# distortion-noise-and-ring-modulator-v1_2.net
KiCad netlist of a schematic drawn in EAGLE
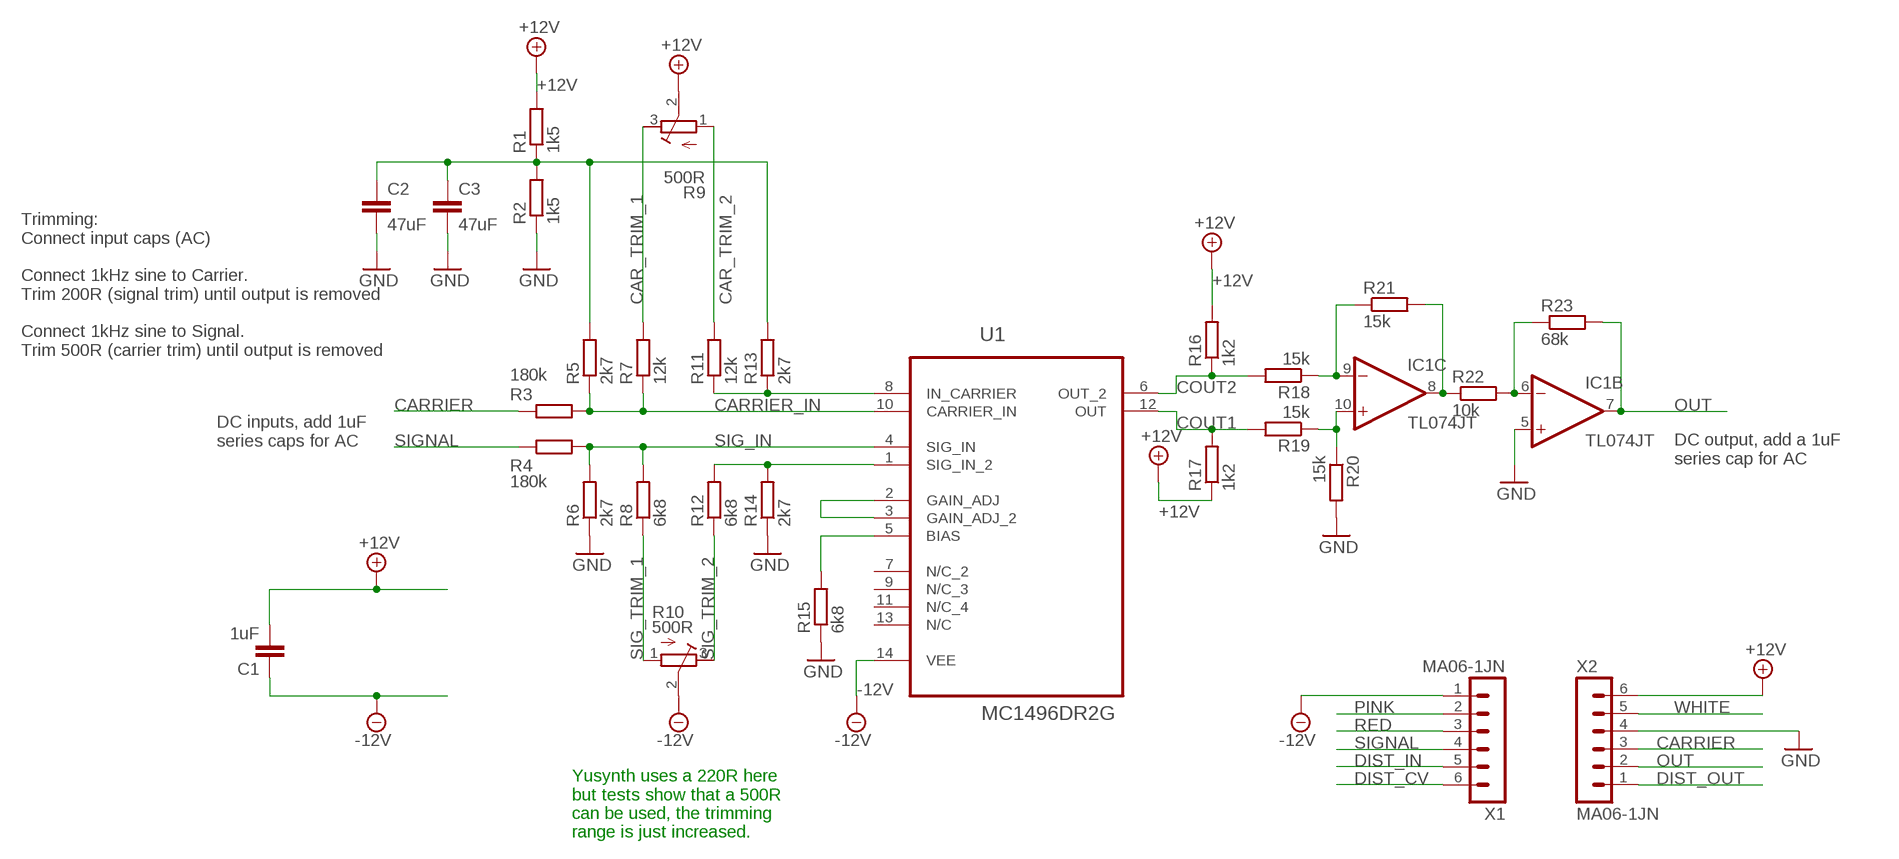
[diagram p0: schematic, sheet 1]
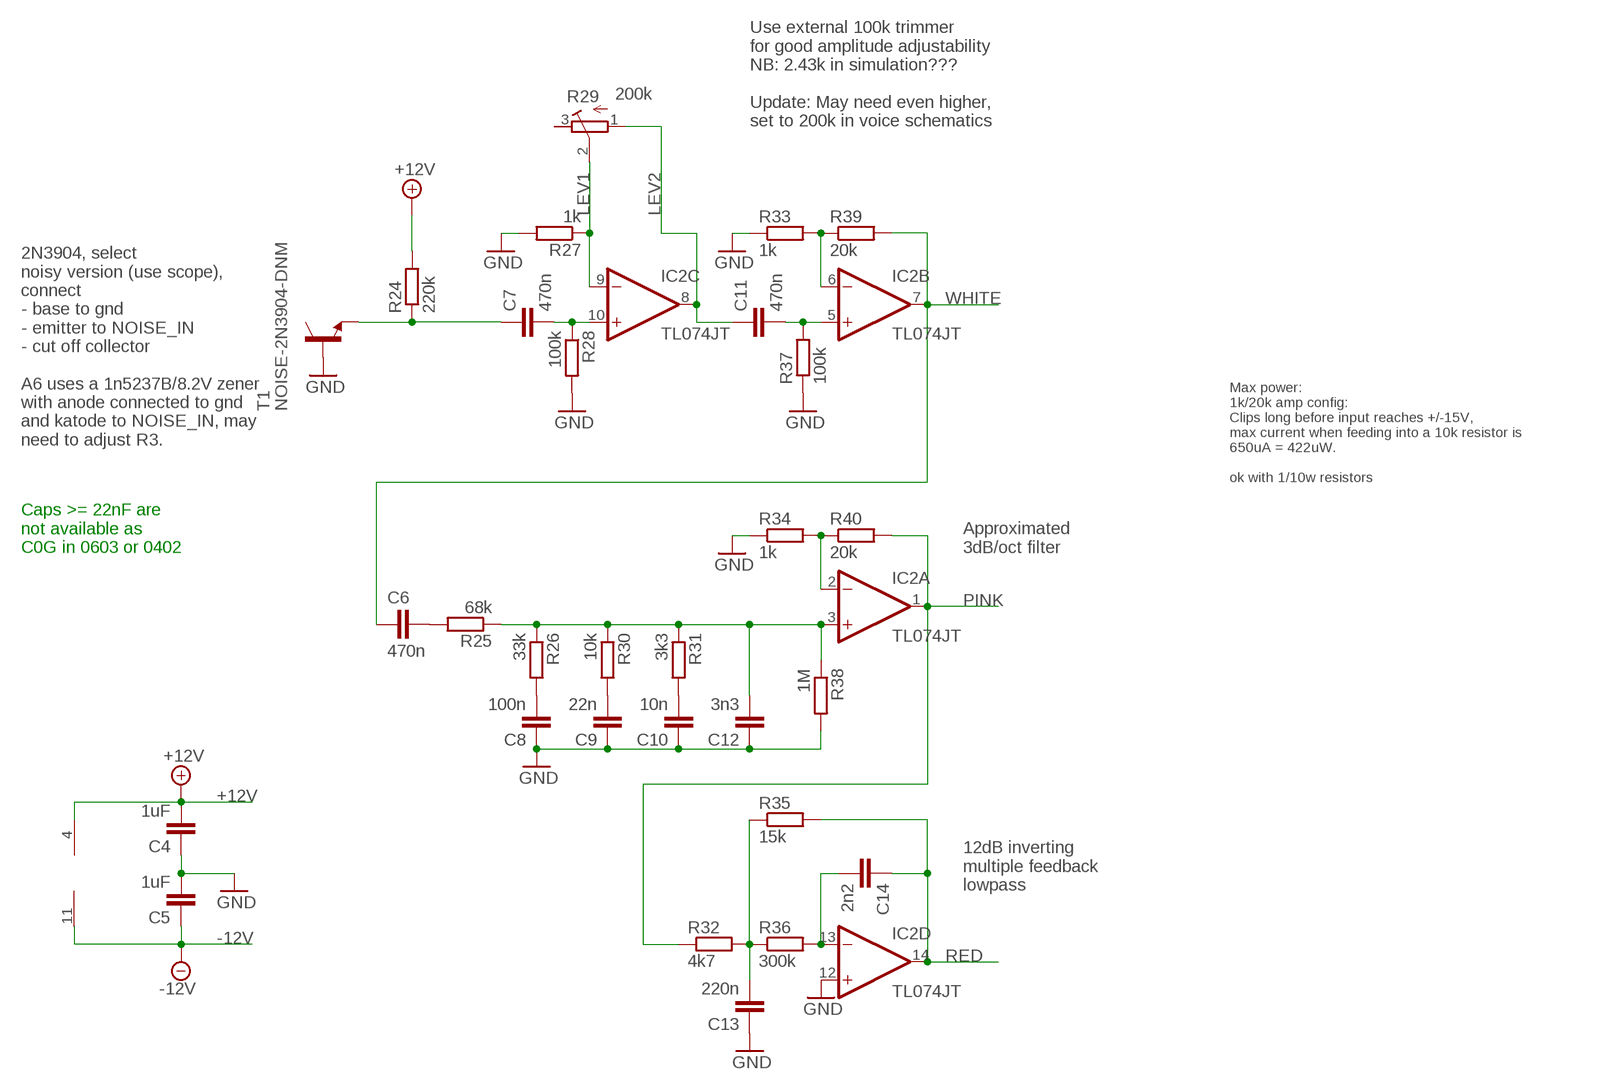
[diagram p1: schematic, sheet 2]
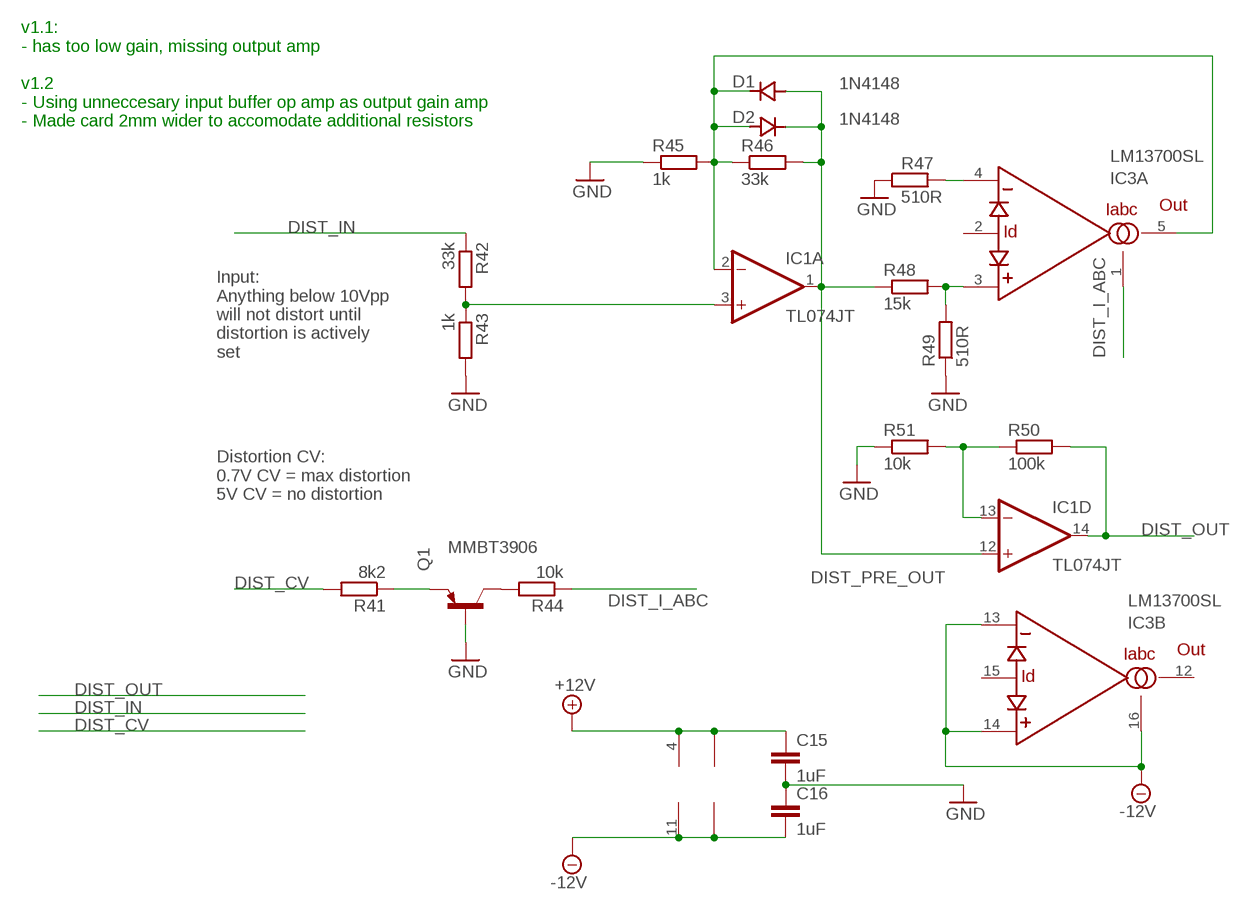
[diagram p2: schematic, sheet 3]

(export (version "E")
  (design (tool "Eeschema 10.0.6"))
  (components
    (comp (ref "C4")
      (value "1uF")
      (footprint "eagle-import:C0402-J")
      (libsource (lib "eagle-import") (part "C-EU-J0402"))
    )
    (comp (ref "C5")
      (value "1uF")
      (footprint "eagle-import:C0402-J")
      (libsource (lib "eagle-import") (part "C-EU-J0402"))
    )
    (comp (ref "C6")
      (value "470n")
      (footprint "eagle-import:C0603-J")
      (libsource (lib "eagle-import") (part "C-EU-J0603"))
    )
    (comp (ref "C7")
      (value "470n")
      (footprint "eagle-import:C0603-J")
      (libsource (lib "eagle-import") (part "C-EU-J0603"))
    )
    (comp (ref "C8")
      (value "100n")
      (footprint "eagle-import:C0402-J")
      (libsource (lib "eagle-import") (part "C-EU-J0402"))
    )
    (comp (ref "C9")
      (value "22n")
      (footprint "eagle-import:C0402-J")
      (libsource (lib "eagle-import") (part "C-EU-J0402"))
    )
    (comp (ref "C10")
      (value "10n")
      (footprint "eagle-import:C0402-J")
      (libsource (lib "eagle-import") (part "C-EU-J0402"))
    )
    (comp (ref "C11")
      (value "470n")
      (footprint "eagle-import:C0603-J")
      (libsource (lib "eagle-import") (part "C-EU-J0603"))
    )
    (comp (ref "C12")
      (value "3n3")
      (footprint "eagle-import:C0603-J")
      (libsource (lib "eagle-import") (part "C-EU-J0603"))
    )
    (comp (ref "C13")
      (value "220n")
      (footprint "eagle-import:C0402-J")
      (libsource (lib "eagle-import") (part "C-EU-J0402"))
    )
    (comp (ref "C14")
      (value "2n2")
      (footprint "eagle-import:C0603-J")
      (libsource (lib "eagle-import") (part "C-EU-J0603"))
    )
    (comp (ref "IC2")
      (value "TL074JT")
      (footprint "eagle-import:TSSOP14J")
      (libsource (lib "eagle-import") (part "TL074JT"))
    )
    (comp (ref "R24")
      (value "220k")
      (footprint "eagle-import:R0603")
      (libsource (lib "eagle-import") (part "R-EU_R0603"))
    )
    (comp (ref "R25")
      (value "68k")
      (footprint "eagle-import:R0603")
      (libsource (lib "eagle-import") (part "R-EU_R0603"))
    )
    (comp (ref "R26")
      (value "33k")
      (footprint "eagle-import:R0402")
      (libsource (lib "eagle-import") (part "R-EU_R0402"))
    )
    (comp (ref "R27")
      (value "1k")
      (footprint "eagle-import:R0402")
      (libsource (lib "eagle-import") (part "R-EU_R0402"))
    )
    (comp (ref "R28")
      (value "100k")
      (footprint "eagle-import:R0402")
      (libsource (lib "eagle-import") (part "R-EU_R0402"))
    )
    (comp (ref "R29")
      (value "200k")
      (footprint "eagle-import:RTRIM3296W")
      (libsource (lib "eagle-import") (part "R-TRIMM3296W"))
    )
    (comp (ref "R30")
      (value "10k")
      (footprint "eagle-import:R0402")
      (libsource (lib "eagle-import") (part "R-EU_R0402"))
    )
    (comp (ref "R31")
      (value "3k3")
      (footprint "eagle-import:R0402")
      (libsource (lib "eagle-import") (part "R-EU_R0402"))
    )
    (comp (ref "R32")
      (value "4k7")
      (footprint "eagle-import:R0402")
      (libsource (lib "eagle-import") (part "R-EU_R0402"))
    )
    (comp (ref "R33")
      (value "1k")
      (footprint "eagle-import:R0402")
      (libsource (lib "eagle-import") (part "R-EU_R0402"))
    )
    (comp (ref "R34")
      (value "1k")
      (footprint "eagle-import:R0402")
      (libsource (lib "eagle-import") (part "R-EU_R0402"))
    )
    (comp (ref "R35")
      (value "15k")
      (footprint "eagle-import:R0402")
      (libsource (lib "eagle-import") (part "R-EU_R0402"))
    )
    (comp (ref "R36")
      (value "300k")
      (footprint "eagle-import:R0603")
      (libsource (lib "eagle-import") (part "R-EU_R0603"))
    )
    (comp (ref "R37")
      (value "100k")
      (footprint "eagle-import:R0402")
      (libsource (lib "eagle-import") (part "R-EU_R0402"))
    )
    (comp (ref "R38")
      (value "1M")
      (footprint "eagle-import:R0402")
      (libsource (lib "eagle-import") (part "R-EU_R0402"))
    )
    (comp (ref "R39")
      (value "20k")
      (footprint "eagle-import:R0402")
      (libsource (lib "eagle-import") (part "R-EU_R0402"))
    )
    (comp (ref "R40")
      (value "20k")
      (footprint "eagle-import:R0402")
      (libsource (lib "eagle-import") (part "R-EU_R0402"))
    )
    (comp (ref "T1")
      (value "NOISE-2N3904-DNM")
      (footprint "eagle-import:NOISE-2N3904-J")
      (libsource (lib "eagle-import") (part "NOISE-2N3904"))
    )
    (comp (ref "C1")
      (value "1uF")
      (footprint "eagle-import:C0402-J")
      (libsource (lib "eagle-import") (part "C-EU-J0402"))
    )
    (comp (ref "C2")
      (value "47uF")
      (footprint "eagle-import:C1206")
      (libsource (lib "eagle-import") (part "C-EUC1206"))
    )
    (comp (ref "C3")
      (value "47uF")
      (footprint "eagle-import:C1206")
      (libsource (lib "eagle-import") (part "C-EUC1206"))
    )
    (comp (ref "IC1")
      (value "TL074JT")
      (footprint "eagle-import:TSSOP14J")
      (libsource (lib "eagle-import") (part "TL074JT"))
    )
    (comp (ref "R1")
      (value "1k5")
      (footprint "eagle-import:R0402")
      (libsource (lib "eagle-import") (part "R-EU_R0402"))
    )
    (comp (ref "R2")
      (value "1k5")
      (footprint "eagle-import:R0402")
      (libsource (lib "eagle-import") (part "R-EU_R0402"))
    )
    (comp (ref "R3")
      (value "180k")
      (footprint "eagle-import:R0402")
      (libsource (lib "eagle-import") (part "R-EU_R0402"))
    )
    (comp (ref "R4")
      (value "180k")
      (footprint "eagle-import:R0402")
      (libsource (lib "eagle-import") (part "R-EU_R0402"))
    )
    (comp (ref "R5")
      (value "2k7")
      (footprint "eagle-import:R0603")
      (libsource (lib "eagle-import") (part "R-EU_R0603"))
    )
    (comp (ref "R6")
      (value "2k7")
      (footprint "eagle-import:R0603")
      (libsource (lib "eagle-import") (part "R-EU_R0603"))
    )
    (comp (ref "R7")
      (value "12k")
      (footprint "eagle-import:R0402")
      (libsource (lib "eagle-import") (part "R-EU_R0402"))
    )
    (comp (ref "R8")
      (value "6k8")
      (footprint "eagle-import:R0603")
      (libsource (lib "eagle-import") (part "R-EU_R0603"))
    )
    (comp (ref "R9")
      (value "500R")
      (footprint "eagle-import:RTRIM3296X")
      (libsource (lib "eagle-import") (part "R-TRIMM3296X"))
    )
    (comp (ref "R10")
      (value "500R")
      (footprint "eagle-import:RTRIM3296X")
      (libsource (lib "eagle-import") (part "R-TRIMM3296X"))
    )
    (comp (ref "R11")
      (value "12k")
      (footprint "eagle-import:R0402")
      (libsource (lib "eagle-import") (part "R-EU_R0402"))
    )
    (comp (ref "R12")
      (value "6k8")
      (footprint "eagle-import:R0603")
      (libsource (lib "eagle-import") (part "R-EU_R0603"))
    )
    (comp (ref "R13")
      (value "2k7")
      (footprint "eagle-import:R0603")
      (libsource (lib "eagle-import") (part "R-EU_R0603"))
    )
    (comp (ref "R14")
      (value "2k7")
      (footprint "eagle-import:R0603")
      (libsource (lib "eagle-import") (part "R-EU_R0603"))
    )
    (comp (ref "R15")
      (value "6k8")
      (footprint "eagle-import:R0603")
      (libsource (lib "eagle-import") (part "R-EU_R0603"))
    )
    (comp (ref "R16")
      (value "1k2")
      (footprint "eagle-import:R0603")
      (libsource (lib "eagle-import") (part "R-EU_R0603"))
    )
    (comp (ref "R17")
      (value "1k2")
      (footprint "eagle-import:R0603")
      (libsource (lib "eagle-import") (part "R-EU_R0603"))
    )
    (comp (ref "R18")
      (value "15k")
      (footprint "eagle-import:R0402")
      (libsource (lib "eagle-import") (part "R-EU_R0402"))
    )
    (comp (ref "R19")
      (value "15k")
      (footprint "eagle-import:R0402")
      (libsource (lib "eagle-import") (part "R-EU_R0402"))
    )
    (comp (ref "R20")
      (value "15k")
      (footprint "eagle-import:R0402")
      (libsource (lib "eagle-import") (part "R-EU_R0402"))
    )
    (comp (ref "R21")
      (value "15k")
      (footprint "eagle-import:R0402")
      (libsource (lib "eagle-import") (part "R-EU_R0402"))
    )
    (comp (ref "R22")
      (value "10k")
      (footprint "eagle-import:R0402")
      (libsource (lib "eagle-import") (part "R-EU_R0402"))
    )
    (comp (ref "R23")
      (value "68k")
      (footprint "eagle-import:R0603")
      (libsource (lib "eagle-import") (part "R-EU_R0603"))
    )
    (comp (ref "U1")
      (value "MC1496DR2G")
      (footprint "eagle-import:SOIC127P600X175-14N")
      (libsource (lib "eagle-import") (part "MC1496DR2G"))
    )
    (comp (ref "X1")
      (value "MA06-1JN")
      (footprint "eagle-import:MA06N-1J")
      (libsource (lib "eagle-import") (part "MA06-1JN"))
    )
    (comp (ref "X2")
      (value "MA06-1JN")
      (footprint "eagle-import:MA06N-1J")
      (libsource (lib "eagle-import") (part "MA06-1JN"))
    )
    (comp (ref "C15")
      (value "1uF")
      (footprint "eagle-import:C0402-J")
      (libsource (lib "eagle-import") (part "C-EU-J0402"))
    )
    (comp (ref "C16")
      (value "1uF")
      (footprint "eagle-import:C0402-J")
      (libsource (lib "eagle-import") (part "C-EU-J0402"))
    )
    (comp (ref "D1")
      (value "1N4148")
      (footprint "eagle-import:SOD323J")
      (libsource (lib "eagle-import") (part "1N4148SOD323"))
    )
    (comp (ref "D2")
      (value "1N4148")
      (footprint "eagle-import:SOD323J")
      (libsource (lib "eagle-import") (part "1N4148SOD323"))
    )
    (comp (ref "IC3")
      (value "LM13700SL")
      (footprint "eagle-import:SO16-NARROW-J")
      (libsource (lib "eagle-import") (part "LM13700SL"))
    )
    (comp (ref "Q1")
      (value "MMBT3906")
      (footprint "eagle-import:SOT23-BEC")
      (libsource (lib "eagle-import") (part "MMBT3906SMDLT1"))
    )
    (comp (ref "R41")
      (value "8k2")
      (footprint "eagle-import:R0603")
      (libsource (lib "eagle-import") (part "R-EU_R0603"))
    )
    (comp (ref "R42")
      (value "33k")
      (footprint "eagle-import:R0402")
      (libsource (lib "eagle-import") (part "R-EU_R0402"))
    )
    (comp (ref "R43")
      (value "1k")
      (footprint "eagle-import:R0402")
      (libsource (lib "eagle-import") (part "R-EU_R0402"))
    )
    (comp (ref "R44")
      (value "10k")
      (footprint "eagle-import:R0402")
      (libsource (lib "eagle-import") (part "R-EU_R0402"))
    )
    (comp (ref "R45")
      (value "1k")
      (footprint "eagle-import:R0402")
      (libsource (lib "eagle-import") (part "R-EU_R0402"))
    )
    (comp (ref "R46")
      (value "33k")
      (footprint "eagle-import:R0402")
      (libsource (lib "eagle-import") (part "R-EU_R0402"))
    )
    (comp (ref "R47")
      (value "510R")
      (footprint "eagle-import:R0402")
      (libsource (lib "eagle-import") (part "R-EU_R0402"))
    )
    (comp (ref "R48")
      (value "15k")
      (footprint "eagle-import:R0402")
      (libsource (lib "eagle-import") (part "R-EU_R0402"))
    )
    (comp (ref "R49")
      (value "510R")
      (footprint "eagle-import:R0402")
      (libsource (lib "eagle-import") (part "R-EU_R0402"))
    )
    (comp (ref "R50")
      (value "100k")
      (footprint "eagle-import:R0402")
      (libsource (lib "eagle-import") (part "R-EU_R0402"))
    )
    (comp (ref "R51")
      (value "10k")
      (footprint "eagle-import:R0402")
      (libsource (lib "eagle-import") (part "R-EU_R0402"))
    )
  )
  (nets
    (net (code "1") (name "+12V") (class "Default")
      (node (ref "C1") (pin "2") (pinfunction "2_2") (pintype "passive"))
      (node (ref "C15") (pin "1") (pinfunction "1_1") (pintype "passive"))
      (node (ref "C4") (pin "2") (pinfunction "2_2") (pintype "passive"))
      (node (ref "IC1") (pin "4") (pinfunction "V+_4") (pintype "power_in"))
      (node (ref "IC2") (pin "4") (pinfunction "V+_4") (pintype "power_in"))
      (node (ref "IC3") (pin "11") (pinfunction "V+_11") (pintype "bidirectional"))
      (node (ref "R1") (pin "2") (pinfunction "2_2") (pintype "passive"))
      (node (ref "R16") (pin "2") (pinfunction "2_2") (pintype "passive"))
      (node (ref "R17") (pin "1") (pinfunction "1_1") (pintype "passive"))
      (node (ref "R24") (pin "2") (pinfunction "2_2") (pintype "passive"))
      (node (ref "R9") (pin "2") (pinfunction "S_2") (pintype "passive"))
      (node (ref "X2") (pin "6") (pinfunction "6_6") (pintype "passive"))
    )
    (net (code "2") (name "-12V") (class "Default")
      (node (ref "C1") (pin "1") (pinfunction "1_1") (pintype "passive"))
      (node (ref "C16") (pin "2") (pinfunction "2_2") (pintype "passive"))
      (node (ref "C5") (pin "1") (pinfunction "1_1") (pintype "passive"))
      (node (ref "IC1") (pin "11") (pinfunction "V-_11") (pintype "power_in"))
      (node (ref "IC2") (pin "11") (pinfunction "V-_11") (pintype "power_in"))
      (node (ref "IC3") (pin "13") (pinfunction "-IN_13") (pintype "bidirectional"))
      (node (ref "IC3") (pin "14") (pinfunction "+IN_14") (pintype "bidirectional"))
      (node (ref "IC3") (pin "16") (pinfunction "IABC_16") (pintype "bidirectional"))
      (node (ref "IC3") (pin "6") (pinfunction "V-_6") (pintype "bidirectional"))
      (node (ref "R10") (pin "2") (pinfunction "S_2") (pintype "passive"))
      (node (ref "U1") (pin "14") (pinfunction "VEE_14") (pintype "passive"))
      (node (ref "X1") (pin "1") (pinfunction "1_1") (pintype "passive"))
    )
    (net (code "3") (name "CARRIER") (class "Default")
      (node (ref "R3") (pin "1") (pinfunction "1_1") (pintype "passive"))
      (node (ref "X2") (pin "3") (pinfunction "3_3") (pintype "passive"))
    )
    (net (code "4") (name "CARRIER_IN") (class "Default")
      (node (ref "R3") (pin "2") (pinfunction "2_2") (pintype "passive"))
      (node (ref "R5") (pin "1") (pinfunction "1_1") (pintype "passive"))
      (node (ref "R7") (pin "1") (pinfunction "1_1") (pintype "passive"))
      (node (ref "U1") (pin "10") (pinfunction "CARRIER_IN_10") (pintype "power_in"))
    )
    (net (code "5") (name "CAR_TRIM_1") (class "Default")
      (node (ref "R7") (pin "2") (pinfunction "2_2") (pintype "passive"))
      (node (ref "R9") (pin "3") (pinfunction "E_3") (pintype "passive"))
    )
    (net (code "6") (name "CAR_TRIM_2") (class "Default")
      (node (ref "R11") (pin "2") (pinfunction "2_2") (pintype "passive"))
      (node (ref "R9") (pin "1") (pinfunction "A_1") (pintype "passive"))
    )
    (net (code "7") (name "COUT1") (class "Default")
      (node (ref "R17") (pin "2") (pinfunction "2_2") (pintype "passive"))
      (node (ref "R19") (pin "2") (pinfunction "2_2") (pintype "passive"))
      (node (ref "U1") (pin "12") (pinfunction "OUT_12") (pintype "output"))
    )
    (net (code "8") (name "COUT2") (class "Default")
      (node (ref "R16") (pin "1") (pinfunction "1_1") (pintype "passive"))
      (node (ref "R18") (pin "2") (pinfunction "2_2") (pintype "passive"))
      (node (ref "U1") (pin "6") (pinfunction "OUT_2_6") (pintype "output"))
    )
    (net (code "9") (name "DIST_CV") (class "Default")
      (node (ref "R41") (pin "2") (pinfunction "2_2") (pintype "passive"))
      (node (ref "X1") (pin "6") (pinfunction "6_6") (pintype "passive"))
    )
    (net (code "10") (name "DIST_IN") (class "Default")
      (node (ref "R42") (pin "1") (pinfunction "1_1") (pintype "passive"))
      (node (ref "X1") (pin "5") (pinfunction "5_5") (pintype "passive"))
    )
    (net (code "11") (name "DIST_I_ABC") (class "Default")
      (node (ref "IC3") (pin "1") (pinfunction "IABC_1") (pintype "bidirectional"))
      (node (ref "R44") (pin "1") (pinfunction "1_1") (pintype "passive"))
    )
    (net (code "12") (name "DIST_OUT") (class "Default")
      (node (ref "IC1") (pin "14") (pinfunction "OUT_14") (pintype "output"))
      (node (ref "R50") (pin "2") (pinfunction "2_2") (pintype "passive"))
      (node (ref "X2") (pin "1") (pinfunction "1_1") (pintype "passive"))
    )
    (net (code "13") (name "DIST_PRE_OUT") (class "Default")
      (node (ref "D1") (pin "2") (pinfunction "A_2") (pintype "passive"))
      (node (ref "D2") (pin "1") (pinfunction "C_1") (pintype "passive"))
      (node (ref "IC1") (pin "1") (pinfunction "OUT_1") (pintype "output"))
      (node (ref "IC1") (pin "12") (pinfunction "+IN_12") (pintype "input"))
      (node (ref "R46") (pin "2") (pinfunction "2_2") (pintype "passive"))
      (node (ref "R48") (pin "1") (pinfunction "1_1") (pintype "passive"))
    )
    (net (code "14") (name "GND") (class "Default")
      (node (ref "C10") (pin "1") (pinfunction "1_1") (pintype "passive"))
      (node (ref "C12") (pin "1") (pinfunction "1_1") (pintype "passive"))
      (node (ref "C13") (pin "1") (pinfunction "1_1") (pintype "passive"))
      (node (ref "C15") (pin "2") (pinfunction "2_2") (pintype "passive"))
      (node (ref "C16") (pin "1") (pinfunction "1_1") (pintype "passive"))
      (node (ref "C2") (pin "2") (pinfunction "2_2") (pintype "passive"))
      (node (ref "C3") (pin "2") (pinfunction "2_2") (pintype "passive"))
      (node (ref "C4") (pin "1") (pinfunction "1_1") (pintype "passive"))
      (node (ref "C5") (pin "2") (pinfunction "2_2") (pintype "passive"))
      (node (ref "C8") (pin "1") (pinfunction "1_1") (pintype "passive"))
      (node (ref "C9") (pin "1") (pinfunction "1_1") (pintype "passive"))
      (node (ref "IC1") (pin "5") (pinfunction "+IN_5") (pintype "input"))
      (node (ref "IC2") (pin "12") (pinfunction "+IN_12") (pintype "input"))
      (node (ref "Q1") (pin "B") (pinfunction "B_B") (pintype "passive"))
      (node (ref "R14") (pin "1") (pinfunction "1_1") (pintype "passive"))
      (node (ref "R15") (pin "1") (pinfunction "1_1") (pintype "passive"))
      (node (ref "R2") (pin "1") (pinfunction "1_1") (pintype "passive"))
      (node (ref "R20") (pin "2") (pinfunction "2_2") (pintype "passive"))
      (node (ref "R27") (pin "2") (pinfunction "2_2") (pintype "passive"))
      (node (ref "R28") (pin "2") (pinfunction "2_2") (pintype "passive"))
      (node (ref "R33") (pin "1") (pinfunction "1_1") (pintype "passive"))
      (node (ref "R34") (pin "1") (pinfunction "1_1") (pintype "passive"))
      (node (ref "R37") (pin "1") (pinfunction "1_1") (pintype "passive"))
      (node (ref "R38") (pin "2") (pinfunction "2_2") (pintype "passive"))
      (node (ref "R43") (pin "2") (pinfunction "2_2") (pintype "passive"))
      (node (ref "R45") (pin "1") (pinfunction "1_1") (pintype "passive"))
      (node (ref "R47") (pin "1") (pinfunction "1_1") (pintype "passive"))
      (node (ref "R49") (pin "1") (pinfunction "1_1") (pintype "passive"))
      (node (ref "R51") (pin "1") (pinfunction "1_1") (pintype "passive"))
      (node (ref "R6") (pin "1") (pinfunction "1_1") (pintype "passive"))
      (node (ref "T1") (pin "B") (pinfunction "B_B") (pintype "passive"))
      (node (ref "X2") (pin "4") (pinfunction "4_4") (pintype "passive"))
    )
    (net (code "15") (name "LEV1") (class "Default")
      (node (ref "IC2") (pin "9") (pinfunction "-IN_9") (pintype "input"))
      (node (ref "R27") (pin "1") (pinfunction "1_1") (pintype "passive"))
      (node (ref "R29") (pin "2") (pinfunction "S_2") (pintype "passive"))
    )
    (net (code "16") (name "LEV2") (class "Default")
      (node (ref "C11") (pin "1") (pinfunction "1_1") (pintype "passive"))
      (node (ref "IC2") (pin "8") (pinfunction "OUT_8") (pintype "output"))
      (node (ref "R29") (pin "1") (pinfunction "A_1") (pintype "passive"))
    )
    (net (code "17") (name "Net-(C2-Pad1)") (class "Default")
      (node (ref "C2") (pin "1") (pinfunction "1_1") (pintype "passive"))
      (node (ref "C3") (pin "1") (pinfunction "1_1") (pintype "passive"))
      (node (ref "R1") (pin "1") (pinfunction "1_1") (pintype "passive"))
      (node (ref "R13") (pin "2") (pinfunction "2_2") (pintype "passive"))
      (node (ref "R2") (pin "2") (pinfunction "2_2") (pintype "passive"))
      (node (ref "R5") (pin "2") (pinfunction "2_2") (pintype "passive"))
    )
    (net (code "18") (name "Net-(C6-Pad2)") (class "Default")
      (node (ref "C6") (pin "2") (pinfunction "2_2") (pintype "passive"))
      (node (ref "R25") (pin "2") (pinfunction "2_2") (pintype "passive"))
    )
    (net (code "19") (name "Net-(C7-Pad1)") (class "Default")
      (node (ref "C7") (pin "1") (pinfunction "1_1") (pintype "passive"))
      (node (ref "R24") (pin "1") (pinfunction "1_1") (pintype "passive"))
      (node (ref "T1") (pin "E") (pinfunction "E_E") (pintype "passive"))
    )
    (net (code "20") (name "Net-(C8-Pad2)") (class "Default")
      (node (ref "C8") (pin "2") (pinfunction "2_2") (pintype "passive"))
      (node (ref "R26") (pin "2") (pinfunction "2_2") (pintype "passive"))
    )
    (net (code "21") (name "Net-(C9-Pad2)") (class "Default")
      (node (ref "C9") (pin "2") (pinfunction "2_2") (pintype "passive"))
      (node (ref "R30") (pin "2") (pinfunction "2_2") (pintype "passive"))
    )
    (net (code "22") (name "Net-(C10-Pad2)") (class "Default")
      (node (ref "C10") (pin "2") (pinfunction "2_2") (pintype "passive"))
      (node (ref "R31") (pin "2") (pinfunction "2_2") (pintype "passive"))
    )
    (net (code "23") (name "Net-(C13-Pad2)") (class "Default")
      (node (ref "C13") (pin "2") (pinfunction "2_2") (pintype "passive"))
      (node (ref "R32") (pin "2") (pinfunction "2_2") (pintype "passive"))
      (node (ref "R35") (pin "1") (pinfunction "1_1") (pintype "passive"))
      (node (ref "R36") (pin "1") (pinfunction "1_1") (pintype "passive"))
    )
    (net (code "24") (name "Net-(D1-C)") (class "Default")
      (node (ref "D1") (pin "1") (pinfunction "C_1") (pintype "passive"))
      (node (ref "D2") (pin "2") (pinfunction "A_2") (pintype "passive"))
      (node (ref "IC1") (pin "2") (pinfunction "-IN_2") (pintype "input"))
      (node (ref "IC3") (pin "5") (pinfunction "OUT_5") (pintype "bidirectional"))
      (node (ref "R45") (pin "2") (pinfunction "2_2") (pintype "passive"))
      (node (ref "R46") (pin "1") (pinfunction "1_1") (pintype "passive"))
    )
    (net (code "25") (name "Net-(IC1A-+IN)") (class "Default")
      (node (ref "IC1") (pin "3") (pinfunction "+IN_3") (pintype "input"))
      (node (ref "R42") (pin "2") (pinfunction "2_2") (pintype "passive"))
      (node (ref "R43") (pin "1") (pinfunction "1_1") (pintype "passive"))
    )
    (net (code "26") (name "Net-(IC1B--IN)") (class "Default")
      (node (ref "IC1") (pin "6") (pinfunction "-IN_6") (pintype "input"))
      (node (ref "R22") (pin "2") (pinfunction "2_2") (pintype "passive"))
      (node (ref "R23") (pin "1") (pinfunction "1_1") (pintype "passive"))
    )
    (net (code "27") (name "Net-(IC1C-+IN)") (class "Default")
      (node (ref "IC1") (pin "10") (pinfunction "+IN_10") (pintype "input"))
      (node (ref "R19") (pin "1") (pinfunction "1_1") (pintype "passive"))
      (node (ref "R20") (pin "1") (pinfunction "1_1") (pintype "passive"))
    )
    (net (code "28") (name "Net-(IC1C--IN)") (class "Default")
      (node (ref "IC1") (pin "9") (pinfunction "-IN_9") (pintype "input"))
      (node (ref "R18") (pin "1") (pinfunction "1_1") (pintype "passive"))
      (node (ref "R21") (pin "1") (pinfunction "1_1") (pintype "passive"))
    )
    (net (code "29") (name "Net-(IC1C-OUT)") (class "Default")
      (node (ref "IC1") (pin "8") (pinfunction "OUT_8") (pintype "output"))
      (node (ref "R21") (pin "2") (pinfunction "2_2") (pintype "passive"))
      (node (ref "R22") (pin "1") (pinfunction "1_1") (pintype "passive"))
    )
    (net (code "30") (name "Net-(IC1D--IN)") (class "Default")
      (node (ref "IC1") (pin "13") (pinfunction "-IN_13") (pintype "input"))
      (node (ref "R50") (pin "1") (pinfunction "1_1") (pintype "passive"))
      (node (ref "R51") (pin "2") (pinfunction "2_2") (pintype "passive"))
    )
    (net (code "31") (name "Net-(IC2A-+IN)") (class "Default")
      (node (ref "C12") (pin "2") (pinfunction "2_2") (pintype "passive"))
      (node (ref "IC2") (pin "3") (pinfunction "+IN_3") (pintype "input"))
      (node (ref "R25") (pin "1") (pinfunction "1_1") (pintype "passive"))
      (node (ref "R26") (pin "1") (pinfunction "1_1") (pintype "passive"))
      (node (ref "R30") (pin "1") (pinfunction "1_1") (pintype "passive"))
      (node (ref "R31") (pin "1") (pinfunction "1_1") (pintype "passive"))
      (node (ref "R38") (pin "1") (pinfunction "1_1") (pintype "passive"))
    )
    (net (code "32") (name "Net-(IC2A--IN)") (class "Default")
      (node (ref "IC2") (pin "2") (pinfunction "-IN_2") (pintype "input"))
      (node (ref "R34") (pin "2") (pinfunction "2_2") (pintype "passive"))
      (node (ref "R40") (pin "1") (pinfunction "1_1") (pintype "passive"))
    )
    (net (code "33") (name "Net-(IC2B-+IN)") (class "Default")
      (node (ref "C11") (pin "2") (pinfunction "2_2") (pintype "passive"))
      (node (ref "IC2") (pin "5") (pinfunction "+IN_5") (pintype "input"))
      (node (ref "R37") (pin "2") (pinfunction "2_2") (pintype "passive"))
    )
    (net (code "34") (name "Net-(IC2B--IN)") (class "Default")
      (node (ref "IC2") (pin "6") (pinfunction "-IN_6") (pintype "input"))
      (node (ref "R33") (pin "2") (pinfunction "2_2") (pintype "passive"))
      (node (ref "R39") (pin "1") (pinfunction "1_1") (pintype "passive"))
    )
    (net (code "35") (name "Net-(IC2C-+IN)") (class "Default")
      (node (ref "C7") (pin "2") (pinfunction "2_2") (pintype "passive"))
      (node (ref "IC2") (pin "10") (pinfunction "+IN_10") (pintype "input"))
      (node (ref "R28") (pin "1") (pinfunction "1_1") (pintype "passive"))
    )
    (net (code "36") (name "Net-(IC2D--IN)") (class "Default")
      (node (ref "C14") (pin "2") (pinfunction "2_2") (pintype "passive"))
      (node (ref "IC2") (pin "13") (pinfunction "-IN_13") (pintype "input"))
      (node (ref "R36") (pin "2") (pinfunction "2_2") (pintype "passive"))
    )
    (net (code "37") (name "Net-(IC3A-+IN)") (class "Default")
      (node (ref "IC3") (pin "3") (pinfunction "+IN_3") (pintype "bidirectional"))
      (node (ref "R48") (pin "2") (pinfunction "2_2") (pintype "passive"))
      (node (ref "R49") (pin "2") (pinfunction "2_2") (pintype "passive"))
    )
    (net (code "38") (name "Net-(IC3A--IN)") (class "Default")
      (node (ref "IC3") (pin "4") (pinfunction "-IN_4") (pintype "bidirectional"))
      (node (ref "R47") (pin "2") (pinfunction "2_2") (pintype "passive"))
    )
    (net (code "39") (name "Net-(Q1-PadC)") (class "Default")
      (node (ref "Q1") (pin "C") (pinfunction "C_C") (pintype "passive"))
      (node (ref "R44") (pin "2") (pinfunction "2_2") (pintype "passive"))
    )
    (net (code "40") (name "Net-(Q1-PadE)") (class "Default")
      (node (ref "Q1") (pin "E") (pinfunction "E_E") (pintype "passive"))
      (node (ref "R41") (pin "1") (pinfunction "1_1") (pintype "passive"))
    )
    (net (code "41") (name "Net-(U1-BIAS)") (class "Default")
      (node (ref "R15") (pin "2") (pinfunction "2_2") (pintype "passive"))
      (node (ref "U1") (pin "5") (pinfunction "BIAS_5") (pintype "input"))
    )
    (net (code "42") (name "Net-(U1-GAIN_ADJ)") (class "Default")
      (node (ref "U1") (pin "2") (pinfunction "GAIN_ADJ_2") (pintype "input"))
      (node (ref "U1") (pin "3") (pinfunction "GAIN_ADJ_2_3") (pintype "input"))
    )
    (net (code "43") (name "Net-(U1-IN_CARRIER)") (class "Default")
      (node (ref "R11") (pin "1") (pinfunction "1_1") (pintype "passive"))
      (node (ref "R13") (pin "1") (pinfunction "1_1") (pintype "passive"))
      (node (ref "U1") (pin "8") (pinfunction "IN_CARRIER_8") (pintype "power_in"))
    )
    (net (code "44") (name "Net-(U1-SIG_IN_2)") (class "Default")
      (node (ref "R12") (pin "2") (pinfunction "2_2") (pintype "passive"))
      (node (ref "R14") (pin "2") (pinfunction "2_2") (pintype "passive"))
      (node (ref "U1") (pin "1") (pinfunction "SIG_IN_2_1") (pintype "input"))
    )
    (net (code "45") (name "OUT") (class "Default")
      (node (ref "IC1") (pin "7") (pinfunction "OUT_7") (pintype "output"))
      (node (ref "R23") (pin "2") (pinfunction "2_2") (pintype "passive"))
      (node (ref "X2") (pin "2") (pinfunction "2_2") (pintype "passive"))
    )
    (net (code "46") (name "PINK") (class "Default")
      (node (ref "IC2") (pin "1") (pinfunction "OUT_1") (pintype "output"))
      (node (ref "R32") (pin "1") (pinfunction "1_1") (pintype "passive"))
      (node (ref "R40") (pin "2") (pinfunction "2_2") (pintype "passive"))
      (node (ref "X1") (pin "2") (pinfunction "2_2") (pintype "passive"))
    )
    (net (code "47") (name "RED") (class "Default")
      (node (ref "C14") (pin "1") (pinfunction "1_1") (pintype "passive"))
      (node (ref "IC2") (pin "14") (pinfunction "OUT_14") (pintype "output"))
      (node (ref "R35") (pin "2") (pinfunction "2_2") (pintype "passive"))
      (node (ref "X1") (pin "3") (pinfunction "3_3") (pintype "passive"))
    )
    (net (code "48") (name "SIGNAL") (class "Default")
      (node (ref "R4") (pin "1") (pinfunction "1_1") (pintype "passive"))
      (node (ref "X1") (pin "4") (pinfunction "4_4") (pintype "passive"))
    )
    (net (code "49") (name "SIG_IN") (class "Default")
      (node (ref "R4") (pin "2") (pinfunction "2_2") (pintype "passive"))
      (node (ref "R6") (pin "2") (pinfunction "2_2") (pintype "passive"))
      (node (ref "R8") (pin "2") (pinfunction "2_2") (pintype "passive"))
      (node (ref "U1") (pin "4") (pinfunction "SIG_IN_4") (pintype "input"))
    )
    (net (code "50") (name "SIG_TRIM_1") (class "Default")
      (node (ref "R10") (pin "1") (pinfunction "A_1") (pintype "passive"))
      (node (ref "R8") (pin "1") (pinfunction "1_1") (pintype "passive"))
    )
    (net (code "51") (name "SIG_TRIM_2") (class "Default")
      (node (ref "R10") (pin "3") (pinfunction "E_3") (pintype "passive"))
      (node (ref "R12") (pin "1") (pinfunction "1_1") (pintype "passive"))
    )
    (net (code "52") (name "WHITE") (class "Default")
      (node (ref "C6") (pin "1") (pinfunction "1_1") (pintype "passive"))
      (node (ref "IC2") (pin "7") (pinfunction "OUT_7") (pintype "output"))
      (node (ref "R39") (pin "2") (pinfunction "2_2") (pintype "passive"))
      (node (ref "X2") (pin "5") (pinfunction "5_5") (pintype "passive"))
    )
    (net (code "53") (name "unconnected-(IC3A-ID-Pad2)") (class "Default")
      (node (ref "IC3") (pin "2") (pinfunction "ID_2") (pintype "bidirectional"))
    )
    (net (code "54") (name "unconnected-(IC3B-ID-Pad15)") (class "Default")
      (node (ref "IC3") (pin "15") (pinfunction "ID_15") (pintype "bidirectional"))
    )
    (net (code "55") (name "unconnected-(IC3B-OUT-Pad12)") (class "Default")
      (node (ref "IC3") (pin "12") (pinfunction "OUT_12") (pintype "bidirectional"))
    )
    (net (code "56") (name "unconnected-(R29-E-Pad3)") (class "Default")
      (node (ref "R29") (pin "3") (pinfunction "E_3") (pintype "passive"))
    )
    (net (code "57") (name "unconnected-(U1-N{slash}C-Pad13)") (class "Default")
      (node (ref "U1") (pin "13") (pinfunction "N/C_13") (pintype "no_connect"))
    )
    (net (code "58") (name "unconnected-(U1-N{slash}C_2-Pad7)") (class "Default")
      (node (ref "U1") (pin "7") (pinfunction "N/C_2_7") (pintype "no_connect"))
    )
    (net (code "59") (name "unconnected-(U1-N{slash}C_3-Pad9)") (class "Default")
      (node (ref "U1") (pin "9") (pinfunction "N/C_3_9") (pintype "no_connect"))
    )
    (net (code "60") (name "unconnected-(U1-N{slash}C_4-Pad11)") (class "Default")
      (node (ref "U1") (pin "11") (pinfunction "N/C_4_11") (pintype "no_connect"))
    )
  )
)
